# Radio.net
KiCad netlist of a schematic drawn in Altium Designer
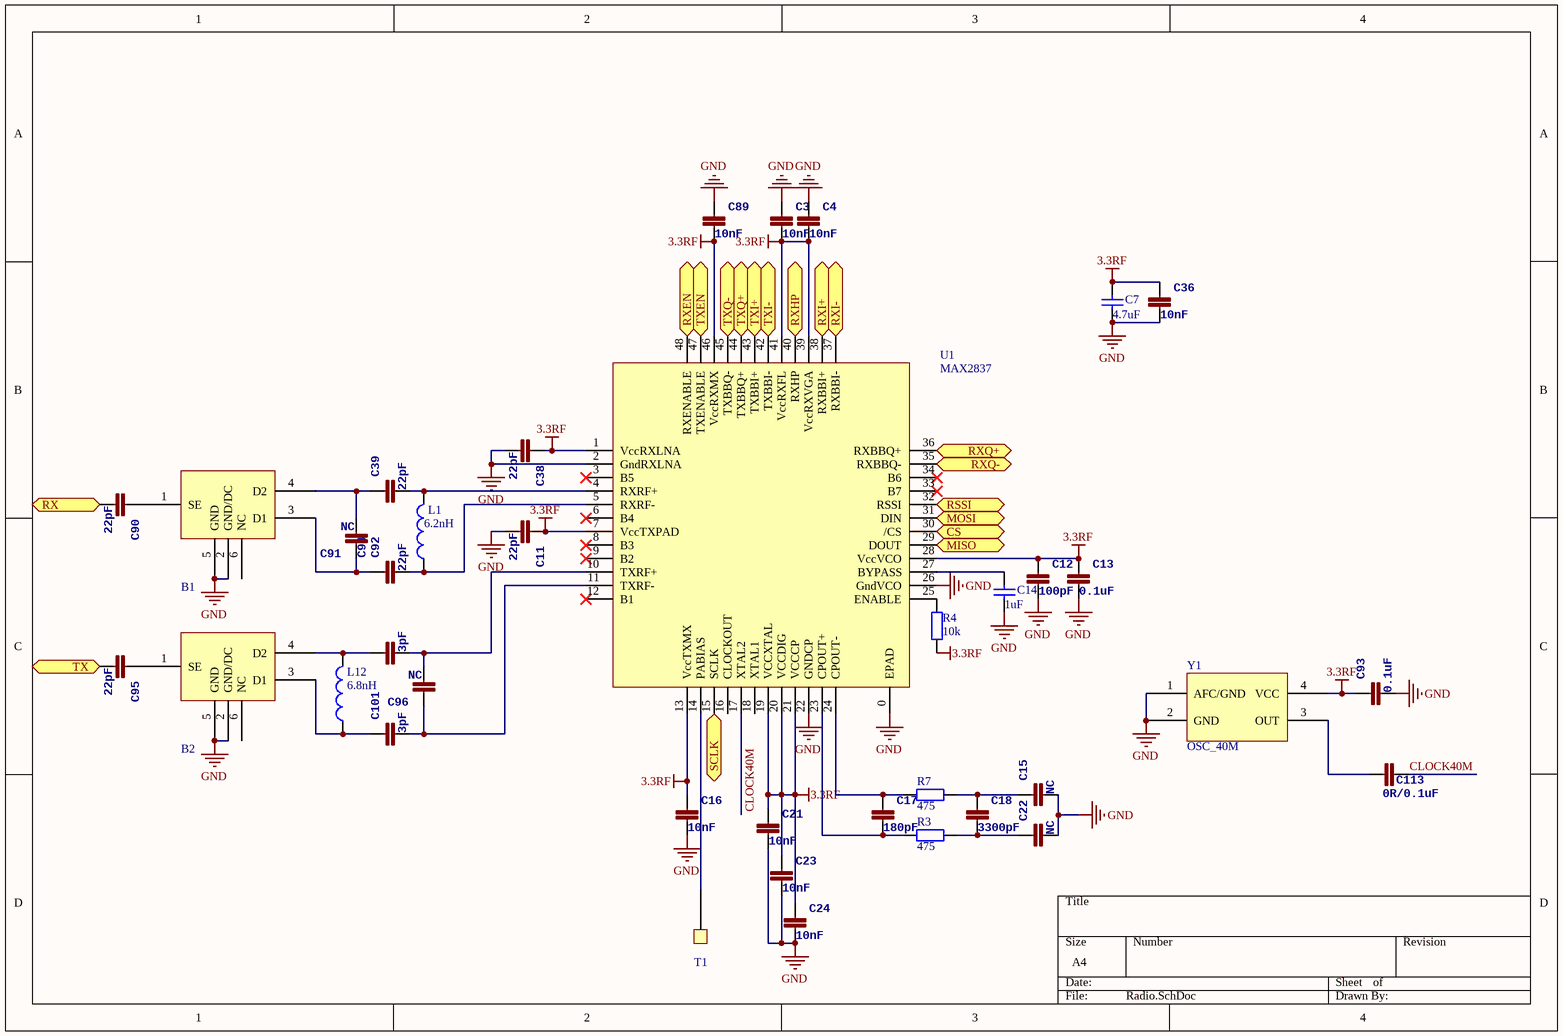
[diagram p0: Radio.SchDoc]

(export (version "E")
  (design (tool "Eeschema 10.0.6"))
  (components
    (comp (ref "B1")
      (value "Balun")
      (footprint "HHM1711D1/HHM1732B1")
      (libsource (lib "F4SDR") (part "Balun"))
    )
    (comp (ref "B2")
      (value "Balun")
      (footprint "HHM1711D1/HHM1732B1")
      (libsource (lib "F4SDR") (part "Balun"))
    )
    (comp (ref "C3")
      (value "10nF")
      (footprint "0402")
      (description "<b>Capacitor</b>\nStandard 0603 ceramic capacitor, and 0.1\" leaded capacitor.")
      (fields (field (name "PARTNO") "CC0402ZRY5V7BB104"))
      (libsource (lib "") (part "CAP0402-CAP_1"))
    )
    (comp (ref "C4")
      (value "10nF")
      (footprint "0402")
      (description "<b>Capacitor</b>\nStandard 0603 ceramic capacitor, and 0.1\" leaded capacitor.")
      (fields (field (name "PARTNO") "CC0402ZRY5V7BB104"))
      (libsource (lib "") (part "CAP0402-CAP_1"))
    )
    (comp (ref "C7")
      (value "4.7uF")
      (footprint "0603")
      (description "Capacitor")
      (fields (field (name "PUBLISHER") "Altium Limited"))
      (libsource (lib "RTC6705") (part "Cap"))
    )
    (comp (ref "C11")
      (value "22pF")
      (footprint "0402")
      (description "<b>Capacitor</b>\nStandard 0603 ceramic capacitor, and 0.1\" leaded capacitor.")
      (fields (field (name "PARTNO") "CC0402ZRY5V7BB104"))
      (libsource (lib "") (part "CAP0402-CAP_2"))
    )
    (comp (ref "C12")
      (value "100pF")
      (footprint "0402")
      (description "<b>Capacitor</b>\nStandard 0603 ceramic capacitor, and 0.1\" leaded capacitor.")
      (fields (field (name "PARTNO") "CC0402ZRY5V7BB104"))
      (libsource (lib "") (part "CAP0402-CAP_1"))
    )
    (comp (ref "C13")
      (value "0.1uF")
      (footprint "0402")
      (description "<b>Capacitor</b>\nStandard 0603 ceramic capacitor, and 0.1\" leaded capacitor.")
      (fields (field (name "PARTNO") "CC0402ZRY5V7BB104"))
      (libsource (lib "") (part "CAP0402-CAP_1"))
    )
    (comp (ref "C14")
      (value "1uF")
      (footprint "0603")
      (description "Capacitor")
      (fields (field (name "PUBLISHER") "Altium Limited"))
      (libsource (lib "RTC6705") (part "Cap"))
    )
    (comp (ref "C15")
      (value "NC")
      (footprint "0402")
      (description "<b>Capacitor</b>\nStandard 0603 ceramic capacitor, and 0.1\" leaded capacitor.")
      (fields (field (name "PARTNO") "CC0402ZRY5V7BB104"))
      (libsource (lib "pixhawk2") (part "CAP0402-CAP"))
    )
    (comp (ref "C16")
      (value "10nF")
      (footprint "0402")
      (description "<b>Capacitor</b>\nStandard 0603 ceramic capacitor, and 0.1\" leaded capacitor.")
      (fields (field (name "PARTNO") "CC0402ZRY5V7BB104"))
      (libsource (lib "") (part "CAP0402-CAP_1"))
    )
    (comp (ref "C17")
      (value "180pF")
      (footprint "0402")
      (description "<b>Capacitor</b>\nStandard 0603 ceramic capacitor, and 0.1\" leaded capacitor.")
      (fields (field (name "PARTNO") "CC0402ZRY5V7BB104"))
      (libsource (lib "") (part "CAP0402-CAP_1"))
    )
    (comp (ref "C18")
      (value "3300pF")
      (footprint "0402")
      (description "<b>Capacitor</b>\nStandard 0603 ceramic capacitor, and 0.1\" leaded capacitor.")
      (fields (field (name "PARTNO") "CC0402ZRY5V7BB104"))
      (libsource (lib "") (part "CAP0402-CAP_1"))
    )
    (comp (ref "C21")
      (value "10nF")
      (footprint "0402")
      (description "<b>Capacitor</b>\nStandard 0603 ceramic capacitor, and 0.1\" leaded capacitor.")
      (fields (field (name "PARTNO") "CC0402ZRY5V7BB104"))
      (libsource (lib "") (part "CAP0402-CAP_1"))
    )
    (comp (ref "C22")
      (value "NC")
      (footprint "0402")
      (description "<b>Capacitor</b>\nStandard 0603 ceramic capacitor, and 0.1\" leaded capacitor.")
      (fields (field (name "PARTNO") "CC0402ZRY5V7BB104"))
      (libsource (lib "pixhawk2") (part "CAP0402-CAP"))
    )
    (comp (ref "C23")
      (value "10nF")
      (footprint "0402")
      (description "<b>Capacitor</b>\nStandard 0603 ceramic capacitor, and 0.1\" leaded capacitor.")
      (fields (field (name "PARTNO") "CC0402ZRY5V7BB104"))
      (libsource (lib "") (part "CAP0402-CAP_1"))
    )
    (comp (ref "C24")
      (value "10nF")
      (footprint "0402")
      (description "<b>Capacitor</b>\nStandard 0603 ceramic capacitor, and 0.1\" leaded capacitor.")
      (fields (field (name "PARTNO") "CC0402ZRY5V7BB104"))
      (libsource (lib "") (part "CAP0402-CAP_1"))
    )
    (comp (ref "C36")
      (value "10nF")
      (footprint "0402")
      (description "<b>Capacitor</b>\nStandard 0603 ceramic capacitor, and 0.1\" leaded capacitor.")
      (fields (field (name "PARTNO") "CC0402ZRY5V7BB104"))
      (libsource (lib "") (part "CAP0402-CAP_1"))
    )
    (comp (ref "C38")
      (value "22pF")
      (footprint "0402")
      (description "<b>Capacitor</b>\nStandard 0603 ceramic capacitor, and 0.1\" leaded capacitor.")
      (fields (field (name "PARTNO") "CC0402ZRY5V7BB104"))
      (libsource (lib "") (part "CAP0402-CAP_2"))
    )
    (comp (ref "C39")
      (value "22pF")
      (footprint "0402")
      (description "<b>Capacitor</b>\nStandard 0603 ceramic capacitor, and 0.1\" leaded capacitor.")
      (fields (field (name "PARTNO") "CC0402ZRY5V7BB104"))
      (libsource (lib "pixhawk2") (part "CAP0402-CAP"))
    )
    (comp (ref "C89")
      (value "10nF")
      (footprint "0402")
      (description "<b>Capacitor</b>\nStandard 0603 ceramic capacitor, and 0.1\" leaded capacitor.")
      (fields (field (name "PARTNO") "CC0402ZRY5V7BB104"))
      (libsource (lib "") (part "CAP0402-CAP_1"))
    )
    (comp (ref "C90")
      (value "22pF")
      (footprint "0402")
      (description "<b>Capacitor</b>\nStandard 0603 ceramic capacitor, and 0.1\" leaded capacitor.")
      (fields (field (name "PARTNO") "CC0402ZRY5V7BB104"))
      (libsource (lib "") (part "CAP0402-CAP_2"))
    )
    (comp (ref "C91")
      (value "NC")
      (footprint "0402")
      (description "<b>Capacitor</b>\nStandard 0603 ceramic capacitor, and 0.1\" leaded capacitor.")
      (fields (field (name "PARTNO") "CC0402ZRY5V7BB104"))
      (libsource (lib "") (part "CAP0402-CAP_3"))
    )
    (comp (ref "C92")
      (value "22pF")
      (footprint "0402")
      (description "<b>Capacitor</b>\nStandard 0603 ceramic capacitor, and 0.1\" leaded capacitor.")
      (fields (field (name "PARTNO") "CC0402ZRY5V7BB104"))
      (libsource (lib "pixhawk2") (part "CAP0402-CAP"))
    )
    (comp (ref "C93")
      (value "0.1uF")
      (footprint "0402")
      (description "<b>Capacitor</b>\nStandard 0603 ceramic capacitor, and 0.1\" leaded capacitor.")
      (fields (field (name "PARTNO") "CC0402ZRY5V7BB104"))
      (libsource (lib "pixhawk2") (part "CAP0402-CAP"))
    )
    (comp (ref "C94")
      (value "3pF")
      (footprint "0402")
      (description "<b>Capacitor</b>\nStandard 0603 ceramic capacitor, and 0.1\" leaded capacitor.")
      (fields (field (name "PARTNO") "CC0402ZRY5V7BB104"))
      (libsource (lib "pixhawk2") (part "CAP0402-CAP"))
    )
    (comp (ref "C95")
      (value "22pF")
      (footprint "0402")
      (description "<b>Capacitor</b>\nStandard 0603 ceramic capacitor, and 0.1\" leaded capacitor.")
      (fields (field (name "PARTNO") "CC0402ZRY5V7BB104"))
      (libsource (lib "") (part "CAP0402-CAP_2"))
    )
    (comp (ref "C96")
      (value "NC")
      (footprint "0402")
      (description "<b>Capacitor</b>\nStandard 0603 ceramic capacitor, and 0.1\" leaded capacitor.")
      (fields (field (name "PARTNO") "CC0402ZRY5V7BB104"))
      (libsource (lib "") (part "CAP0402-CAP_3"))
    )
    (comp (ref "C101")
      (value "3pF")
      (footprint "0402")
      (description "<b>Capacitor</b>\nStandard 0603 ceramic capacitor, and 0.1\" leaded capacitor.")
      (fields (field (name "PARTNO") "CC0402ZRY5V7BB104"))
      (libsource (lib "pixhawk2") (part "CAP0402-CAP"))
    )
    (comp (ref "C113")
      (value "0R/0.1uF")
      (footprint "0402")
      (description "<b>Capacitor</b>\nStandard 0603 ceramic capacitor, and 0.1\" leaded capacitor.")
      (fields (field (name "PARTNO") "CC0402ZRY5V7BB104"))
      (libsource (lib "pixhawk2") (part "CAP0402-CAP"))
    )
    (comp (ref "L1")
      (value "6.2nH")
      (footprint "0402")
      (description "Inductor")
      (fields (field (name "PUBLISHER") "Altium Limited"))
      (libsource (lib "Miscellaneous Devices") (part "Inductor"))
    )
    (comp (ref "L12")
      (value "6.8nH")
      (footprint "0402")
      (description "Inductor")
      (fields (field (name "Comment") "NC") (field (name "PUBLISHER") "Altium Limited"))
      (libsource (lib "Miscellaneous Devices") (part "Inductor"))
    )
    (comp (ref "R3")
      (value "475")
      (footprint "0402")
      (description "Resistor")
      (fields (field (name "PUBLISHER") "Altium Limited"))
      (libsource (lib "Miscellaneous Devices") (part "Res2"))
    )
    (comp (ref "R4")
      (value "10k")
      (footprint "0402")
      (description "Resistor")
      (fields (field (name "PUBLISHER") "Altium Limited"))
      (libsource (lib "") (part "Res2_1"))
    )
    (comp (ref "R7")
      (value "475")
      (footprint "0402")
      (description "Resistor")
      (fields (field (name "PUBLISHER") "Altium Limited"))
      (libsource (lib "Miscellaneous Devices") (part "Res2"))
    )
    (comp (ref "T1") (value "PABIAS") (footprint "TestPad - 1mm") (libsource (lib "sch") (part "TestPad")))
    (comp (ref "U1") (value "MAX2837") (footprint "MAX2837") (libsource (lib "F4SDR") (part "MAX2837")))
    (comp (ref "Y1") (value "OSC_40M") (footprint "TXC_7Q") (libsource (lib "F4SDR") (part "OSC_40M")))
  )
  (nets
    (net (code "1") (name "/CLOCK40M") (class "Default")
      (node (ref "C113") (pin "2") (pinfunction "2_2") (pintype "passive"))
      (node (ref "U1") (pin "17") (pinfunction "XTAL2_17") (pintype "passive"))
    )
    (net (code "2") (name "/CS") (class "Default")
      (node (ref "U1") (pin "30") (pinfunction "/CS_30") (pintype "passive"))
    )
    (net (code "3") (name "/MISO") (class "Default")
      (node (ref "U1") (pin "29") (pinfunction "DOUT_29") (pintype "passive"))
    )
    (net (code "4") (name "/MOSI") (class "Default")
      (node (ref "U1") (pin "31") (pinfunction "DIN_31") (pintype "passive"))
    )
    (net (code "5") (name "/RSSI") (class "Default")
      (node (ref "U1") (pin "32") (pinfunction "RSSI_32") (pintype "passive"))
    )
    (net (code "6") (name "/RX") (class "Default")
      (node (ref "C90") (pin "2") (pinfunction "2_2") (pintype "passive"))
    )
    (net (code "7") (name "/RXEN") (class "Default")
      (node (ref "U1") (pin "48") (pinfunction "RXENABLE_48") (pintype "passive"))
    )
    (net (code "8") (name "/RXHP") (class "Default")
      (node (ref "U1") (pin "40") (pinfunction "RXHP_40") (pintype "passive"))
    )
    (net (code "9") (name "/RXI+") (class "Default")
      (node (ref "U1") (pin "38") (pinfunction "RXBBI+_38") (pintype "passive"))
    )
    (net (code "10") (name "/RXI-") (class "Default")
      (node (ref "U1") (pin "37") (pinfunction "RXBBI-_37") (pintype "passive"))
    )
    (net (code "11") (name "/RXQ+") (class "Default")
      (node (ref "U1") (pin "36") (pinfunction "RXBBQ+_36") (pintype "passive"))
    )
    (net (code "12") (name "/RXQ-") (class "Default")
      (node (ref "U1") (pin "35") (pinfunction "RXBBQ-_35") (pintype "passive"))
    )
    (net (code "13") (name "/SCLK") (class "Default")
      (node (ref "U1") (pin "15") (pinfunction "SCLK_15") (pintype "passive"))
    )
    (net (code "14") (name "/TX") (class "Default")
      (node (ref "C95") (pin "2") (pinfunction "2_2") (pintype "passive"))
    )
    (net (code "15") (name "/TXEN") (class "Default")
      (node (ref "U1") (pin "47") (pinfunction "TXENABLE_47") (pintype "passive"))
    )
    (net (code "16") (name "/TXI+") (class "Default")
      (node (ref "U1") (pin "43") (pinfunction "TXBBI+_43") (pintype "passive"))
    )
    (net (code "17") (name "/TXI-") (class "Default")
      (node (ref "U1") (pin "42") (pinfunction "TXBBI-_42") (pintype "passive"))
    )
    (net (code "18") (name "/TXQ+") (class "Default")
      (node (ref "U1") (pin "44") (pinfunction "TXBBQ+_44") (pintype "passive"))
    )
    (net (code "19") (name "/TXQ-") (class "Default")
      (node (ref "U1") (pin "45") (pinfunction "TXBBQ-_45") (pintype "passive"))
    )
    (net (code "20") (name "3.3RF") (class "Default")
      (node (ref "C11") (pin "1") (pinfunction "1_1") (pintype "passive"))
      (node (ref "C12") (pin "1") (pinfunction "1_1") (pintype "passive"))
      (node (ref "C13") (pin "1") (pinfunction "1_1") (pintype "passive"))
      (node (ref "C16") (pin "1") (pinfunction "1_1") (pintype "passive"))
      (node (ref "C21") (pin "1") (pinfunction "1_1") (pintype "passive"))
      (node (ref "C23") (pin "1") (pinfunction "1_1") (pintype "passive"))
      (node (ref "C24") (pin "1") (pinfunction "1_1") (pintype "passive"))
      (node (ref "C3") (pin "2") (pinfunction "2_2") (pintype "passive"))
      (node (ref "C36") (pin "1") (pinfunction "1_1") (pintype "passive"))
      (node (ref "C38") (pin "1") (pinfunction "1_1") (pintype "passive"))
      (node (ref "C4") (pin "2") (pinfunction "2_2") (pintype "passive"))
      (node (ref "C7") (pin "2") (pinfunction "2_2") (pintype "passive"))
      (node (ref "C89") (pin "2") (pinfunction "2_2") (pintype "passive"))
      (node (ref "C93") (pin "1") (pinfunction "1_1") (pintype "passive"))
      (node (ref "R4") (pin "1") (pinfunction "1_1") (pintype "passive"))
      (node (ref "U1") (pin "1") (pinfunction "VccRXLNA_1") (pintype "passive"))
      (node (ref "U1") (pin "13") (pinfunction "VccTXMX_13") (pintype "passive"))
      (node (ref "U1") (pin "19") (pinfunction "VCCXTAL_19") (pintype "passive"))
      (node (ref "U1") (pin "20") (pinfunction "VCCDIG_20") (pintype "passive"))
      (node (ref "U1") (pin "21") (pinfunction "VCCCP_21") (pintype "passive"))
      (node (ref "U1") (pin "28") (pinfunction "VccVCO_28") (pintype "passive"))
      (node (ref "U1") (pin "39") (pinfunction "VccRXVGA_39") (pintype "passive"))
      (node (ref "U1") (pin "41") (pinfunction "VccRXFL_41") (pintype "passive"))
      (node (ref "U1") (pin "46") (pinfunction "VccRXMX_46") (pintype "passive"))
      (node (ref "U1") (pin "7") (pinfunction "VccTXPAD_7") (pintype "passive"))
      (node (ref "Y1") (pin "4") (pinfunction "VCC_4") (pintype "passive"))
    )
    (net (code "21") (name "GND") (class "Default")
      (node (ref "B1") (pin "2") (pinfunction "GND/DC_2") (pintype "passive"))
      (node (ref "B1") (pin "5") (pinfunction "GND_5") (pintype "passive"))
      (node (ref "B2") (pin "2") (pinfunction "GND/DC_2") (pintype "passive"))
      (node (ref "B2") (pin "5") (pinfunction "GND_5") (pintype "passive"))
      (node (ref "C11") (pin "2") (pinfunction "2_2") (pintype "passive"))
      (node (ref "C12") (pin "2") (pinfunction "2_2") (pintype "passive"))
      (node (ref "C13") (pin "2") (pinfunction "2_2") (pintype "passive"))
      (node (ref "C14") (pin "1") (pinfunction "1_1") (pintype "passive"))
      (node (ref "C15") (pin "2") (pinfunction "2_2") (pintype "passive"))
      (node (ref "C16") (pin "2") (pinfunction "2_2") (pintype "passive"))
      (node (ref "C21") (pin "2") (pinfunction "2_2") (pintype "passive"))
      (node (ref "C22") (pin "2") (pinfunction "2_2") (pintype "passive"))
      (node (ref "C23") (pin "2") (pinfunction "2_2") (pintype "passive"))
      (node (ref "C24") (pin "2") (pinfunction "2_2") (pintype "passive"))
      (node (ref "C3") (pin "1") (pinfunction "1_1") (pintype "passive"))
      (node (ref "C36") (pin "2") (pinfunction "2_2") (pintype "passive"))
      (node (ref "C38") (pin "2") (pinfunction "2_2") (pintype "passive"))
      (node (ref "C4") (pin "1") (pinfunction "1_1") (pintype "passive"))
      (node (ref "C7") (pin "1") (pinfunction "1_1") (pintype "passive"))
      (node (ref "C89") (pin "1") (pinfunction "1_1") (pintype "passive"))
      (node (ref "C93") (pin "2") (pinfunction "2_2") (pintype "passive"))
      (node (ref "U1") (pin "0") (pinfunction "EPAD_0") (pintype "passive"))
      (node (ref "U1") (pin "2") (pinfunction "GndRXLNA_2") (pintype "passive"))
      (node (ref "U1") (pin "22") (pinfunction "GNDCP_22") (pintype "passive"))
      (node (ref "U1") (pin "26") (pinfunction "GndVCO_26") (pintype "passive"))
      (node (ref "Y1") (pin "1") (pinfunction "AFC/GND_1") (pintype "passive"))
      (node (ref "Y1") (pin "2") (pinfunction "GND_2") (pintype "passive"))
    )
    (net (code "22") (name "Net-(B1-D1)") (class "Default")
      (node (ref "B1") (pin "3") (pinfunction "D1_3") (pintype "passive"))
      (node (ref "C91") (pin "1") (pinfunction "1_1") (pintype "passive"))
      (node (ref "C92") (pin "1") (pinfunction "1_1") (pintype "passive"))
    )
    (net (code "23") (name "Net-(B1-D2)") (class "Default")
      (node (ref "B1") (pin "4") (pinfunction "D2_4") (pintype "passive"))
      (node (ref "C39") (pin "1") (pinfunction "1_1") (pintype "passive"))
      (node (ref "C91") (pin "2") (pinfunction "2_2") (pintype "passive"))
    )
    (net (code "24") (name "Net-(B1-SE)") (class "Default")
      (node (ref "B1") (pin "1") (pinfunction "SE_1") (pintype "passive"))
      (node (ref "C90") (pin "1") (pinfunction "1_1") (pintype "passive"))
    )
    (net (code "25") (name "Net-(B2-D1)") (class "Default")
      (node (ref "B2") (pin "3") (pinfunction "D1_3") (pintype "passive"))
      (node (ref "C101") (pin "1") (pinfunction "1_1") (pintype "passive"))
      (node (ref "L12") (pin "1") (pinfunction "1_1") (pintype "passive"))
    )
    (net (code "26") (name "Net-(B2-D2)") (class "Default")
      (node (ref "B2") (pin "4") (pinfunction "D2_4") (pintype "passive"))
      (node (ref "C94") (pin "1") (pinfunction "1_1") (pintype "passive"))
      (node (ref "L12") (pin "2") (pinfunction "2_2") (pintype "passive"))
    )
    (net (code "27") (name "Net-(B2-SE)") (class "Default")
      (node (ref "B2") (pin "1") (pinfunction "SE_1") (pintype "passive"))
      (node (ref "C95") (pin "1") (pinfunction "1_1") (pintype "passive"))
    )
    (net (code "28") (name "Net-(C15-Pad1)") (class "Default")
      (node (ref "C15") (pin "1") (pinfunction "1_1") (pintype "passive"))
      (node (ref "C18") (pin "1") (pinfunction "1_1") (pintype "passive"))
      (node (ref "R7") (pin "1") (pinfunction "1_1") (pintype "passive"))
    )
    (net (code "29") (name "Net-(C18-Pad2)") (class "Default")
      (node (ref "C18") (pin "2") (pinfunction "2_2") (pintype "passive"))
      (node (ref "C22") (pin "1") (pinfunction "1_1") (pintype "passive"))
      (node (ref "R3") (pin "1") (pinfunction "1_1") (pintype "passive"))
    )
    (net (code "30") (name "Net-(T1-3)") (class "Default")
      (node (ref "T1") (pin "1") (pinfunction "3_1") (pintype "passive"))
      (node (ref "U1") (pin "14") (pinfunction "PABIAS_14") (pintype "passive"))
    )
    (net (code "31") (name "Net-(U1-BYPASS)") (class "Default")
      (node (ref "C14") (pin "2") (pinfunction "2_2") (pintype "passive"))
      (node (ref "U1") (pin "27") (pinfunction "BYPASS_27") (pintype "passive"))
    )
    (net (code "32") (name "Net-(U1-CPOUT+)") (class "Default")
      (node (ref "C17") (pin "2") (pinfunction "2_2") (pintype "passive"))
      (node (ref "R3") (pin "2") (pinfunction "2_2") (pintype "passive"))
      (node (ref "U1") (pin "23") (pinfunction "CPOUT+_23") (pintype "passive"))
    )
    (net (code "33") (name "Net-(U1-CPOUT-)") (class "Default")
      (node (ref "C17") (pin "1") (pinfunction "1_1") (pintype "passive"))
      (node (ref "R7") (pin "2") (pinfunction "2_2") (pintype "passive"))
      (node (ref "U1") (pin "24") (pinfunction "CPOUT-_24") (pintype "passive"))
    )
    (net (code "34") (name "Net-(U1-ENABLE)") (class "Default")
      (node (ref "R4") (pin "2") (pinfunction "2_2") (pintype "passive"))
      (node (ref "U1") (pin "25") (pinfunction "ENABLE_25") (pintype "passive"))
    )
    (net (code "35") (name "Net-(U1-RXRF+)") (class "Default")
      (node (ref "C39") (pin "2") (pinfunction "2_2") (pintype "passive"))
      (node (ref "L1") (pin "2") (pinfunction "2_2") (pintype "passive"))
      (node (ref "U1") (pin "4") (pinfunction "RXRF+_4") (pintype "passive"))
    )
    (net (code "36") (name "Net-(U1-RXRF-)") (class "Default")
      (node (ref "C92") (pin "2") (pinfunction "2_2") (pintype "passive"))
      (node (ref "L1") (pin "1") (pinfunction "1_1") (pintype "passive"))
      (node (ref "U1") (pin "5") (pinfunction "RXRF-_5") (pintype "passive"))
    )
    (net (code "37") (name "Net-(U1-TXRF+)") (class "Default")
      (node (ref "C94") (pin "2") (pinfunction "2_2") (pintype "passive"))
      (node (ref "C96") (pin "2") (pinfunction "2_2") (pintype "passive"))
      (node (ref "U1") (pin "10") (pinfunction "TXRF+_10") (pintype "passive"))
    )
    (net (code "38") (name "Net-(U1-TXRF-)") (class "Default")
      (node (ref "C101") (pin "2") (pinfunction "2_2") (pintype "passive"))
      (node (ref "C96") (pin "1") (pinfunction "1_1") (pintype "passive"))
      (node (ref "U1") (pin "11") (pinfunction "TXRF-_11") (pintype "passive"))
    )
    (net (code "39") (name "Net-(Y1-OUT)") (class "Default")
      (node (ref "C113") (pin "1") (pinfunction "1_1") (pintype "passive"))
      (node (ref "Y1") (pin "3") (pinfunction "OUT_3") (pintype "passive"))
    )
    (net (code "40") (name "unconnected-(B1-NC-Pad6)") (class "Default")
      (node (ref "B1") (pin "6") (pinfunction "NC_6") (pintype "passive"))
    )
    (net (code "41") (name "unconnected-(B2-NC-Pad6)") (class "Default")
      (node (ref "B2") (pin "6") (pinfunction "NC_6") (pintype "passive"))
    )
    (net (code "42") (name "unconnected-(U1-B1-Pad12)") (class "Default")
      (node (ref "U1") (pin "12") (pinfunction "B1_12") (pintype "passive+no_connect"))
    )
    (net (code "43") (name "unconnected-(U1-B2-Pad9)") (class "Default")
      (node (ref "U1") (pin "9") (pinfunction "B2_9") (pintype "passive+no_connect"))
    )
    (net (code "44") (name "unconnected-(U1-B3-Pad8)") (class "Default")
      (node (ref "U1") (pin "8") (pinfunction "B3_8") (pintype "passive+no_connect"))
    )
    (net (code "45") (name "unconnected-(U1-B4-Pad6)") (class "Default")
      (node (ref "U1") (pin "6") (pinfunction "B4_6") (pintype "passive+no_connect"))
    )
    (net (code "46") (name "unconnected-(U1-B5-Pad3)") (class "Default")
      (node (ref "U1") (pin "3") (pinfunction "B5_3") (pintype "passive+no_connect"))
    )
    (net (code "47") (name "unconnected-(U1-B6-Pad34)") (class "Default")
      (node (ref "U1") (pin "34") (pinfunction "B6_34") (pintype "passive+no_connect"))
    )
    (net (code "48") (name "unconnected-(U1-B7-Pad33)") (class "Default")
      (node (ref "U1") (pin "33") (pinfunction "B7_33") (pintype "passive+no_connect"))
    )
    (net (code "49") (name "unconnected-(U1-CLOCKOUT-Pad16)") (class "Default")
      (node (ref "U1") (pin "16") (pinfunction "CLOCKOUT_16") (pintype "passive"))
    )
    (net (code "50") (name "unconnected-(U1-XTAL1-Pad18)") (class "Default")
      (node (ref "U1") (pin "18") (pinfunction "XTAL1_18") (pintype "passive"))
    )
  )
)
